# motor.net
KiCad netlist of a schematic drawn in Altium Designer
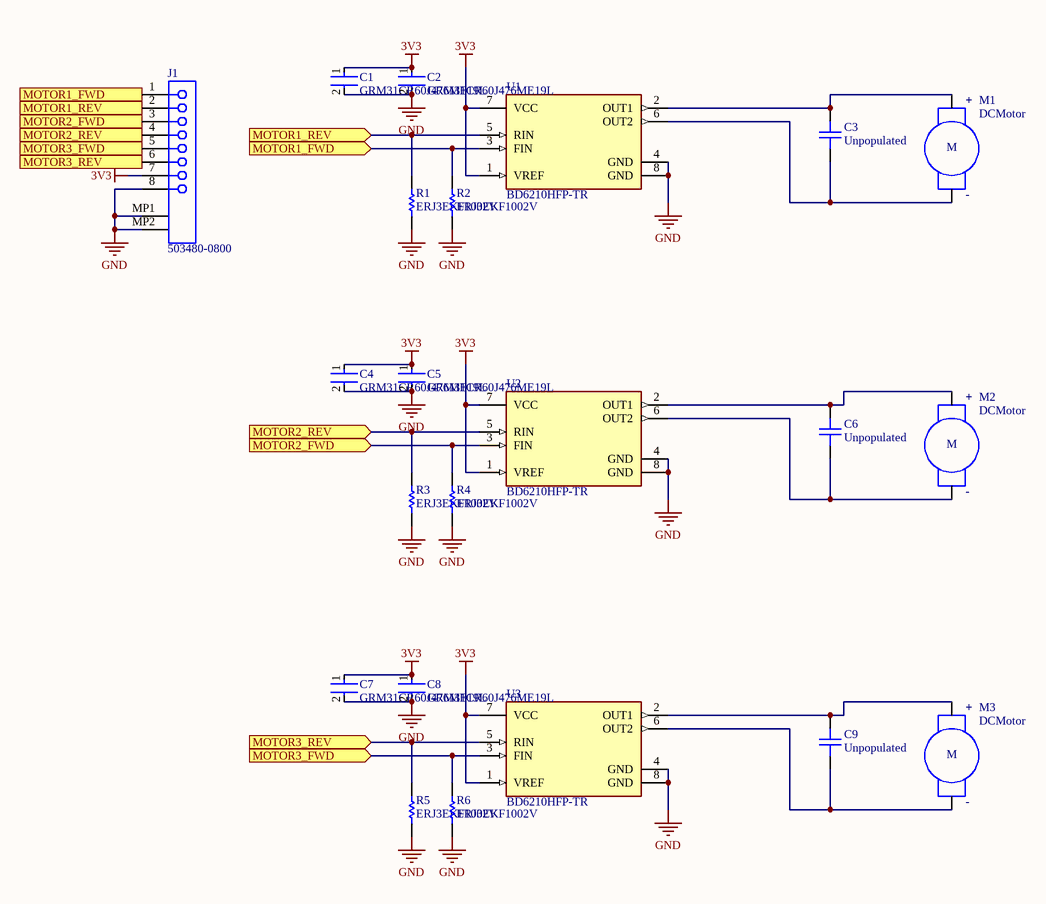
[diagram p0: motor.SchDoc]

(export (version "E")
  (design (tool "Eeschema 10.0.6"))
  (components
    (comp (ref "C1")
      (value "GRM31CR60J476ME19L")
      (footprint "FP-GRM31C-0_2-e0_3_0_8-IPC_C")
      (description "Chip Multilayer Ceramic Capacitors for General Purpose, 1206, 47uF, X5R, 15%, 20%, 6.3V")
      (fields (field (name "TOLERANCE") "20%") (field (name "VOLTAGE") "6.3V"))
      (libsource (lib "Altium Content Vault") (part "02cd4be3c70576c341d710602a673aa"))
    )
    (comp (ref "C2")
      (value "GRM31CR60J476ME19L")
      (footprint "FP-GRM31C-0_2-e0_3_0_8-IPC_C")
      (description "Chip Multilayer Ceramic Capacitors for General Purpose, 1206, 47uF, X5R, 15%, 20%, 6.3V")
      (fields (field (name "TOLERANCE") "20%") (field (name "VOLTAGE") "6.3V"))
      (libsource (lib "Altium Content Vault") (part "02cd4be3c70576c341d710602a673aa"))
    )
    (comp (ref "C3")
      (value "Unpopulated")
      (footprint "TwoTerminal:2012[0805]_M")
      (description "Generic Capacitor")
      (libsource (lib "Passive") (part "Capacitor"))
    )
    (comp (ref "C4")
      (value "GRM31CR60J476ME19L")
      (footprint "FP-GRM31C-0_2-e0_3_0_8-IPC_C")
      (description "Chip Multilayer Ceramic Capacitors for General Purpose, 1206, 47uF, X5R, 15%, 20%, 6.3V")
      (fields (field (name "TOLERANCE") "20%") (field (name "VOLTAGE") "6.3V"))
      (libsource (lib "Altium Content Vault") (part "02cd4be3c70576c341d710602a673aa"))
    )
    (comp (ref "C5")
      (value "GRM31CR60J476ME19L")
      (footprint "FP-GRM31C-0_2-e0_3_0_8-IPC_C")
      (description "Chip Multilayer Ceramic Capacitors for General Purpose, 1206, 47uF, X5R, 15%, 20%, 6.3V")
      (fields (field (name "TOLERANCE") "20%") (field (name "VOLTAGE") "6.3V"))
      (libsource (lib "Altium Content Vault") (part "02cd4be3c70576c341d710602a673aa"))
    )
    (comp (ref "C6")
      (value "Unpopulated")
      (footprint "TwoTerminal:2012[0805]_M")
      (description "Generic Capacitor")
      (libsource (lib "Passive") (part "Capacitor"))
    )
    (comp (ref "C7")
      (value "GRM31CR60J476ME19L")
      (footprint "FP-GRM31C-0_2-e0_3_0_8-IPC_C")
      (description "Chip Multilayer Ceramic Capacitors for General Purpose, 1206, 47uF, X5R, 15%, 20%, 6.3V")
      (fields (field (name "TOLERANCE") "20%") (field (name "VOLTAGE") "6.3V"))
      (libsource (lib "Altium Content Vault") (part "02cd4be3c70576c341d710602a673aa"))
    )
    (comp (ref "C8")
      (value "GRM31CR60J476ME19L")
      (footprint "FP-GRM31C-0_2-e0_3_0_8-IPC_C")
      (description "Chip Multilayer Ceramic Capacitors for General Purpose, 1206, 47uF, X5R, 15%, 20%, 6.3V")
      (fields (field (name "TOLERANCE") "20%") (field (name "VOLTAGE") "6.3V"))
      (libsource (lib "Altium Content Vault") (part "02cd4be3c70576c341d710602a673aa"))
    )
    (comp (ref "C9")
      (value "Unpopulated")
      (footprint "TwoTerminal:2012[0805]_M")
      (description "Generic Capacitor")
      (libsource (lib "Passive") (part "Capacitor"))
    )
    (comp (ref "J1")
      (value "503480-0800")
      (footprint "MOLX-503480-0800")
      (fields (field (name "MANUFACTURER") "Molex"))
      (libsource (lib "Altium Content Vault") (part "MOLX-503480-0800"))
    )
    (comp (ref "M1")
      (value "DCMotor")
      (footprint "CABLE-TERMINAL1x2")
      (description "Generic DC motor")
      (libsource (lib "EPFL") (part "DCMotor"))
    )
    (comp (ref "M2")
      (value "DCMotor")
      (footprint "CABLE-TERMINAL1x2")
      (description "Generic DC motor")
      (libsource (lib "EPFL") (part "DCMotor"))
    )
    (comp (ref "M3")
      (value "DCMotor")
      (footprint "CABLE-TERMINAL1x2")
      (description "Generic DC motor")
      (libsource (lib "EPFL") (part "DCMotor"))
    )
    (comp (ref "R1")
      (value "ERJ3EKF1002V")
      (footprint "RESC1609X55X30ML15T15")
      (description "Chip Resistor, 10 KOhm, +/- 1%, 0.1 W, -55 to 155 degC, 0603 (1608 Metric), RoHS, Tape and Reel")
      (fields (field (name "TOLERANCE") "1%") (field (name "MANUFACTURER") "Panasonic"))
      (libsource (lib "Altium Content Vault") (part "RES-2"))
    )
    (comp (ref "R2")
      (value "ERJ3EKF1002V")
      (footprint "RESC1609X55X30ML15T15")
      (description "Chip Resistor, 10 KOhm, +/- 1%, 0.1 W, -55 to 155 degC, 0603 (1608 Metric), RoHS, Tape and Reel")
      (fields (field (name "TOLERANCE") "1%") (field (name "MANUFACTURER") "Panasonic"))
      (libsource (lib "Altium Content Vault") (part "RES-2"))
    )
    (comp (ref "R3")
      (value "ERJ3EKF1002V")
      (footprint "RESC1609X55X30ML15T15")
      (description "Chip Resistor, 10 KOhm, +/- 1%, 0.1 W, -55 to 155 degC, 0603 (1608 Metric), RoHS, Tape and Reel")
      (fields (field (name "TOLERANCE") "1%") (field (name "MANUFACTURER") "Panasonic"))
      (libsource (lib "Altium Content Vault") (part "RES-2"))
    )
    (comp (ref "R4")
      (value "ERJ3EKF1002V")
      (footprint "RESC1609X55X30ML15T15")
      (description "Chip Resistor, 10 KOhm, +/- 1%, 0.1 W, -55 to 155 degC, 0603 (1608 Metric), RoHS, Tape and Reel")
      (fields (field (name "TOLERANCE") "1%") (field (name "MANUFACTURER") "Panasonic"))
      (libsource (lib "Altium Content Vault") (part "RES-2"))
    )
    (comp (ref "R5")
      (value "ERJ3EKF1002V")
      (footprint "RESC1609X55X30ML15T15")
      (description "Chip Resistor, 10 KOhm, +/- 1%, 0.1 W, -55 to 155 degC, 0603 (1608 Metric), RoHS, Tape and Reel")
      (fields (field (name "TOLERANCE") "1%") (field (name "MANUFACTURER") "Panasonic"))
      (libsource (lib "Altium Content Vault") (part "RES-2"))
    )
    (comp (ref "R6")
      (value "ERJ3EKF1002V")
      (footprint "RESC1609X55X30ML15T15")
      (description "Chip Resistor, 10 KOhm, +/- 1%, 0.1 W, -55 to 155 degC, 0603 (1608 Metric), RoHS, Tape and Reel")
      (fields (field (name "TOLERANCE") "1%") (field (name "MANUFACTURER") "Panasonic"))
      (libsource (lib "Altium Content Vault") (part "RES-2"))
    )
    (comp (ref "U1")
      (value "BD6210HFP-TR")
      (footprint "FP-HRP7-MFG")
      (description "IC MOTOR DRIVER 3V-5.5V HRP7")
      (libsource (lib "Altium Content Vault") (part "5cffe4d96271c81dfd11e73900d312c"))
    )
    (comp (ref "U2")
      (value "BD6210HFP-TR")
      (footprint "FP-HRP7-MFG")
      (description "IC MOTOR DRIVER 3V-5.5V HRP7")
      (libsource (lib "Altium Content Vault") (part "5cffe4d96271c81dfd11e73900d312c"))
    )
    (comp (ref "U3")
      (value "BD6210HFP-TR")
      (footprint "FP-HRP7-MFG")
      (description "IC MOTOR DRIVER 3V-5.5V HRP7")
      (libsource (lib "Altium Content Vault") (part "5cffe4d96271c81dfd11e73900d312c"))
    )
  )
  (nets
    (net (code "1") (name "/MOTOR1_FWD") (class "Default")
      (node (ref "J1") (pin "1") (pinfunction "1_1") (pintype "passive"))
      (node (ref "R2") (pin "2") (pinfunction "2_2") (pintype "passive"))
      (node (ref "U1") (pin "3") (pinfunction "FIN_3") (pintype "input"))
    )
    (net (code "2") (name "/MOTOR1_REV") (class "Default")
      (node (ref "J1") (pin "2") (pinfunction "2_2") (pintype "passive"))
      (node (ref "R1") (pin "2") (pinfunction "2_2") (pintype "passive"))
      (node (ref "U1") (pin "5") (pinfunction "RIN_5") (pintype "input"))
    )
    (net (code "3") (name "/MOTOR2_FWD") (class "Default")
      (node (ref "J1") (pin "3") (pinfunction "3_3") (pintype "passive"))
      (node (ref "R4") (pin "2") (pinfunction "2_2") (pintype "passive"))
      (node (ref "U2") (pin "3") (pinfunction "FIN_3") (pintype "input"))
    )
    (net (code "4") (name "/MOTOR2_REV") (class "Default")
      (node (ref "J1") (pin "4") (pinfunction "4_4") (pintype "passive"))
      (node (ref "R3") (pin "2") (pinfunction "2_2") (pintype "passive"))
      (node (ref "U2") (pin "5") (pinfunction "RIN_5") (pintype "input"))
    )
    (net (code "5") (name "/MOTOR3_FWD") (class "Default")
      (node (ref "J1") (pin "5") (pinfunction "5_5") (pintype "passive"))
      (node (ref "R6") (pin "2") (pinfunction "2_2") (pintype "passive"))
      (node (ref "U3") (pin "3") (pinfunction "FIN_3") (pintype "input"))
    )
    (net (code "6") (name "/MOTOR3_REV") (class "Default")
      (node (ref "J1") (pin "6") (pinfunction "6_6") (pintype "passive"))
      (node (ref "R5") (pin "2") (pinfunction "2_2") (pintype "passive"))
      (node (ref "U3") (pin "5") (pinfunction "RIN_5") (pintype "input"))
    )
    (net (code "7") (name "3V3") (class "Default")
      (node (ref "C1") (pin "1") (pinfunction "1_1") (pintype "passive"))
      (node (ref "C2") (pin "1") (pinfunction "1_1") (pintype "passive"))
      (node (ref "C4") (pin "1") (pinfunction "1_1") (pintype "passive"))
      (node (ref "C5") (pin "1") (pinfunction "1_1") (pintype "passive"))
      (node (ref "C7") (pin "1") (pinfunction "1_1") (pintype "passive"))
      (node (ref "C8") (pin "1") (pinfunction "1_1") (pintype "passive"))
      (node (ref "J1") (pin "7") (pinfunction "7_7") (pintype "passive"))
      (node (ref "U1") (pin "1") (pinfunction "VREF_1") (pintype "input"))
      (node (ref "U1") (pin "7") (pinfunction "VCC_7") (pintype "power_in"))
      (node (ref "U2") (pin "1") (pinfunction "VREF_1") (pintype "input"))
      (node (ref "U2") (pin "7") (pinfunction "VCC_7") (pintype "power_in"))
      (node (ref "U3") (pin "1") (pinfunction "VREF_1") (pintype "input"))
      (node (ref "U3") (pin "7") (pinfunction "VCC_7") (pintype "power_in"))
    )
    (net (code "8") (name "GND") (class "Default")
      (node (ref "C1") (pin "2") (pinfunction "2_2") (pintype "passive"))
      (node (ref "C2") (pin "2") (pinfunction "2_2") (pintype "passive"))
      (node (ref "C4") (pin "2") (pinfunction "2_2") (pintype "passive"))
      (node (ref "C5") (pin "2") (pinfunction "2_2") (pintype "passive"))
      (node (ref "C7") (pin "2") (pinfunction "2_2") (pintype "passive"))
      (node (ref "C8") (pin "2") (pinfunction "2_2") (pintype "passive"))
      (node (ref "J1") (pin "8") (pinfunction "8_8") (pintype "passive"))
      (node (ref "J1") (pin "MP1") (pinfunction "MP1_MP1") (pintype "passive"))
      (node (ref "J1") (pin "MP2") (pinfunction "MP2_MP2") (pintype "passive"))
      (node (ref "R1") (pin "1") (pinfunction "1_1") (pintype "passive"))
      (node (ref "R2") (pin "1") (pinfunction "1_1") (pintype "passive"))
      (node (ref "R3") (pin "1") (pinfunction "1_1") (pintype "passive"))
      (node (ref "R4") (pin "1") (pinfunction "1_1") (pintype "passive"))
      (node (ref "R5") (pin "1") (pinfunction "1_1") (pintype "passive"))
      (node (ref "R6") (pin "1") (pinfunction "1_1") (pintype "passive"))
      (node (ref "U1") (pin "4") (pinfunction "GND_4") (pintype "power_in"))
      (node (ref "U1") (pin "8") (pinfunction "GND_8") (pintype "power_in"))
      (node (ref "U2") (pin "4") (pinfunction "GND_4") (pintype "power_in"))
      (node (ref "U2") (pin "8") (pinfunction "GND_8") (pintype "power_in"))
      (node (ref "U3") (pin "4") (pinfunction "GND_4") (pintype "power_in"))
      (node (ref "U3") (pin "8") (pinfunction "GND_8") (pintype "power_in"))
    )
    (net (code "9") (name "Net-(U1-OUT1)") (class "Default")
      (node (ref "C3") (pin "2") (pinfunction "2_2") (pintype "passive"))
      (node (ref "M1") (pin "+") (pinfunction "+_+") (pintype "passive"))
      (node (ref "U1") (pin "2") (pinfunction "OUT1_2") (pintype "output"))
    )
    (net (code "10") (name "Net-(U1-OUT2)") (class "Default")
      (node (ref "C3") (pin "1") (pinfunction "1_1") (pintype "passive"))
      (node (ref "M1") (pin "-") (pinfunction "-_-") (pintype "passive"))
      (node (ref "U1") (pin "6") (pinfunction "OUT2_6") (pintype "output"))
    )
    (net (code "11") (name "Net-(U2-OUT1)") (class "Default")
      (node (ref "C6") (pin "2") (pinfunction "2_2") (pintype "passive"))
      (node (ref "M2") (pin "+") (pinfunction "+_+") (pintype "passive"))
      (node (ref "U2") (pin "2") (pinfunction "OUT1_2") (pintype "output"))
    )
    (net (code "12") (name "Net-(U2-OUT2)") (class "Default")
      (node (ref "C6") (pin "1") (pinfunction "1_1") (pintype "passive"))
      (node (ref "M2") (pin "-") (pinfunction "-_-") (pintype "passive"))
      (node (ref "U2") (pin "6") (pinfunction "OUT2_6") (pintype "output"))
    )
    (net (code "13") (name "Net-(U3-OUT1)") (class "Default")
      (node (ref "C9") (pin "2") (pinfunction "2_2") (pintype "passive"))
      (node (ref "M3") (pin "+") (pinfunction "+_+") (pintype "passive"))
      (node (ref "U3") (pin "2") (pinfunction "OUT1_2") (pintype "output"))
    )
    (net (code "14") (name "Net-(U3-OUT2)") (class "Default")
      (node (ref "C9") (pin "1") (pinfunction "1_1") (pintype "passive"))
      (node (ref "M3") (pin "-") (pinfunction "-_-") (pintype "passive"))
      (node (ref "U3") (pin "6") (pinfunction "OUT2_6") (pintype "output"))
    )
  )
)
